# display.net
KiCad netlist of a schematic drawn in EAGLE
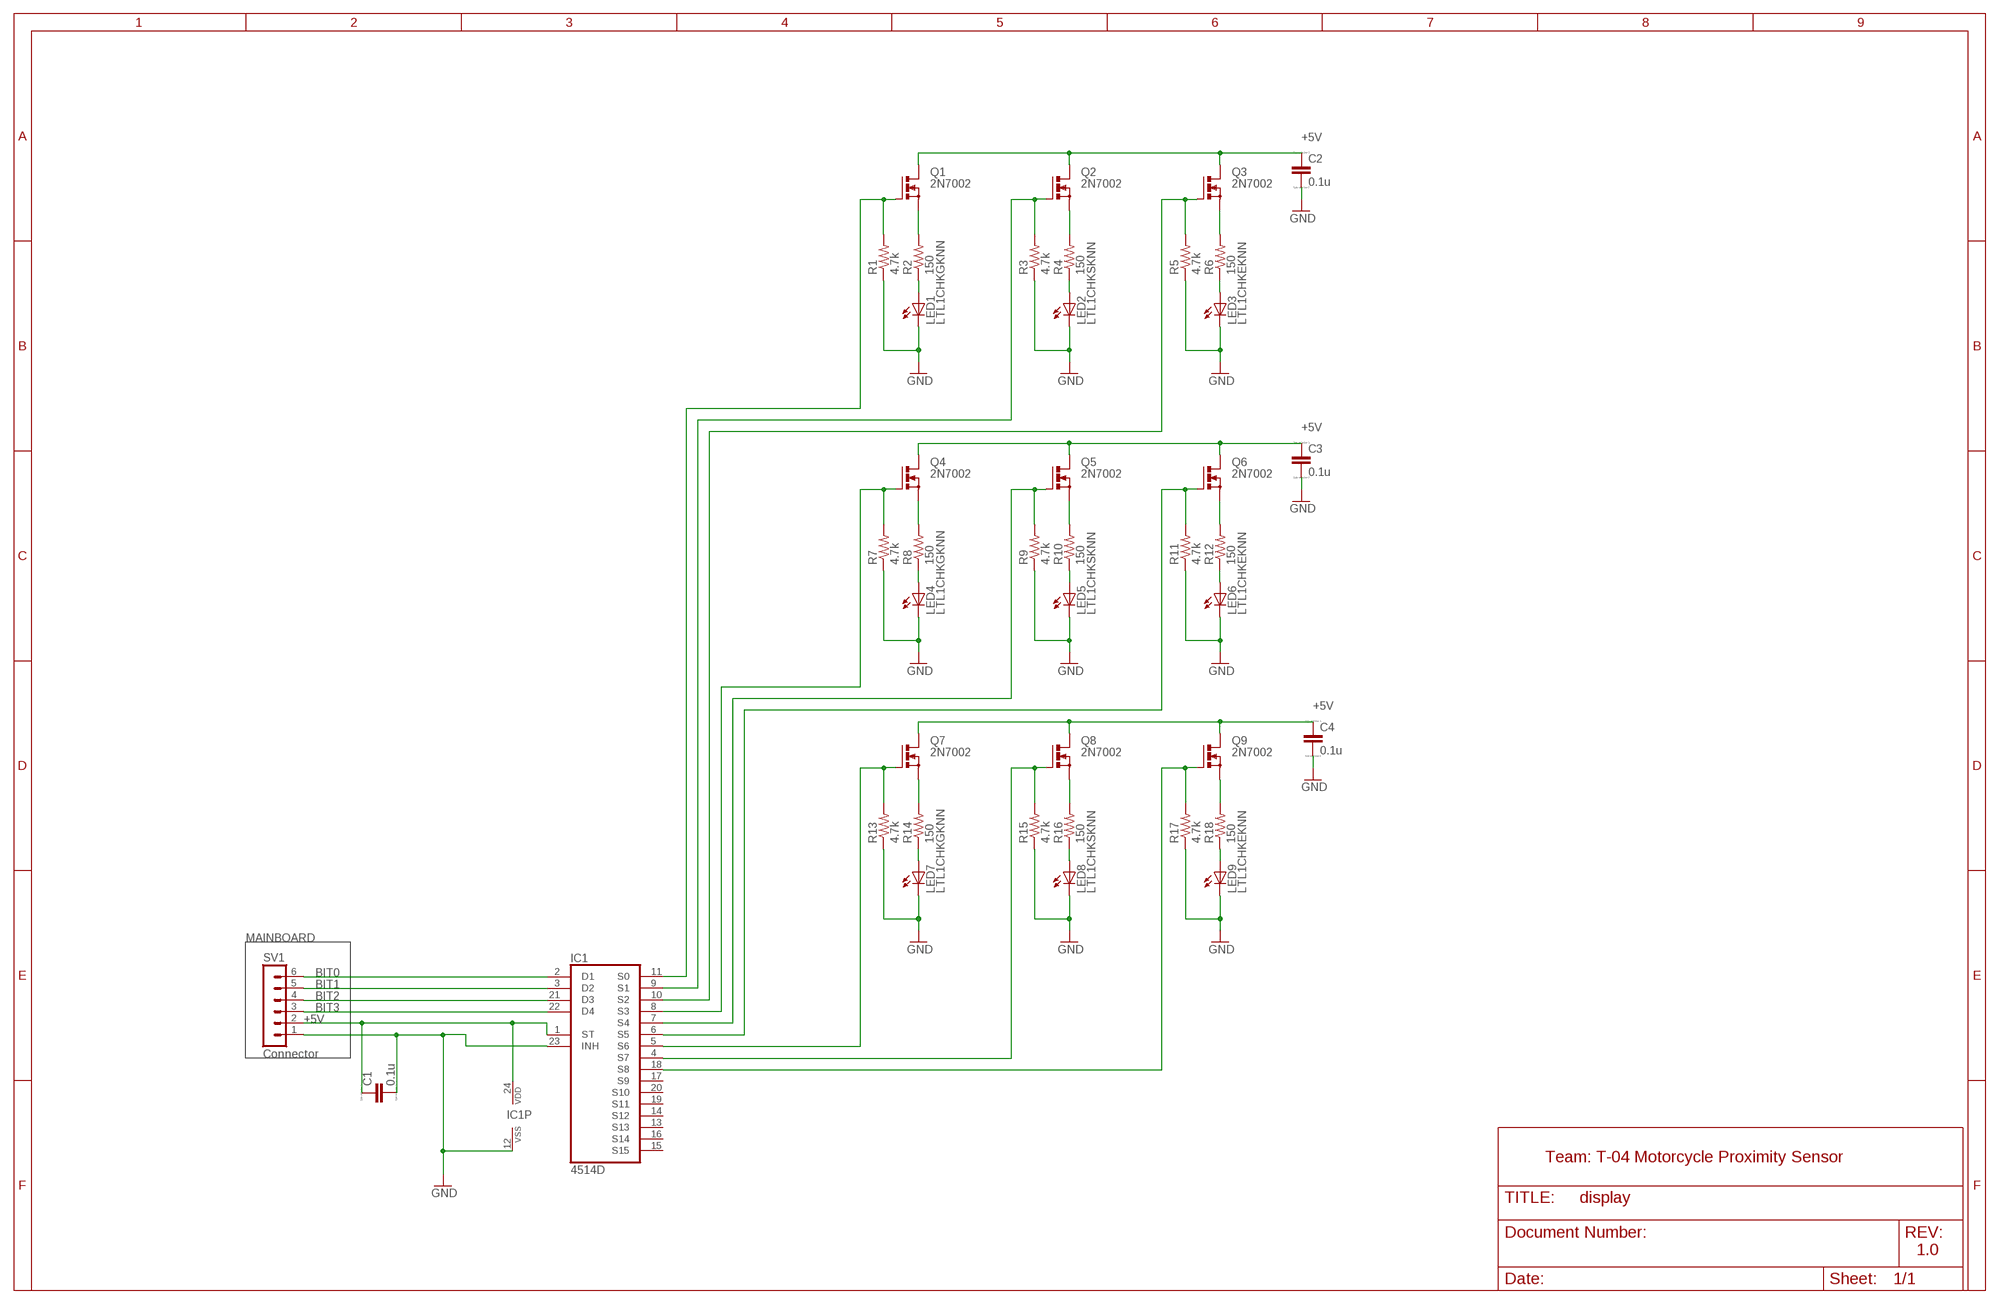
[diagram p0: schematic, sheet 1]

(export (version "E")
  (design (tool "Eeschema 10.0.6"))
  (components
    (comp (ref "C1")
      (value "0.1u")
      (footprint "eagle-import:C3216")
      (libsource (lib "eagle-import") (part "CC3216"))
    )
    (comp (ref "C2")
      (value "0.1u")
      (footprint "eagle-import:C3216")
      (libsource (lib "eagle-import") (part "CC3216"))
    )
    (comp (ref "C3")
      (value "0.1u")
      (footprint "eagle-import:C3216")
      (libsource (lib "eagle-import") (part "CC3216"))
    )
    (comp (ref "C4")
      (value "0.1u")
      (footprint "eagle-import:C3216")
      (libsource (lib "eagle-import") (part "CC3216"))
    )
    (comp (ref "IC1")
      (value "4514D")
      (footprint "eagle-import:SO24W")
      (libsource (lib "eagle-import") (part "4514D"))
    )
    (comp (ref "LED1")
      (value "LTL1CHKGKNN")
      (footprint "eagle-import:1206")
      (libsource (lib "eagle-import") (part "LEDSMT1206"))
    )
    (comp (ref "LED2")
      (value "LTL1CHKSKNN")
      (footprint "eagle-import:1206")
      (libsource (lib "eagle-import") (part "LEDSMT1206"))
    )
    (comp (ref "LED3")
      (value "LTL1CHKEKNN")
      (footprint "eagle-import:1206")
      (libsource (lib "eagle-import") (part "LEDSMT1206"))
    )
    (comp (ref "LED4")
      (value "LTL1CHKGKNN")
      (footprint "eagle-import:1206")
      (libsource (lib "eagle-import") (part "LEDSMT1206"))
    )
    (comp (ref "LED5")
      (value "LTL1CHKSKNN")
      (footprint "eagle-import:1206")
      (libsource (lib "eagle-import") (part "LEDSMT1206"))
    )
    (comp (ref "LED6")
      (value "LTL1CHKEKNN")
      (footprint "eagle-import:1206")
      (libsource (lib "eagle-import") (part "LEDSMT1206"))
    )
    (comp (ref "LED7")
      (value "LTL1CHKGKNN")
      (footprint "eagle-import:1206")
      (libsource (lib "eagle-import") (part "LEDSMT1206"))
    )
    (comp (ref "LED8")
      (value "LTL1CHKSKNN")
      (footprint "eagle-import:1206")
      (libsource (lib "eagle-import") (part "LEDSMT1206"))
    )
    (comp (ref "LED9")
      (value "LTL1CHKEKNN")
      (footprint "eagle-import:1206")
      (libsource (lib "eagle-import") (part "LEDSMT1206"))
    )
    (comp (ref "Q1")
      (value "2N7002")
      (footprint "eagle-import:TO220BV")
      (libsource (lib "eagle-import") (part "BUZ11BV"))
    )
    (comp (ref "Q2")
      (value "2N7002")
      (footprint "eagle-import:TO220BV")
      (libsource (lib "eagle-import") (part "BUZ11BV"))
    )
    (comp (ref "Q3")
      (value "2N7002")
      (footprint "eagle-import:TO220BV")
      (libsource (lib "eagle-import") (part "BUZ11BV"))
    )
    (comp (ref "Q4")
      (value "2N7002")
      (footprint "eagle-import:TO220BV")
      (libsource (lib "eagle-import") (part "BUZ11BV"))
    )
    (comp (ref "Q5")
      (value "2N7002")
      (footprint "eagle-import:TO220BV")
      (libsource (lib "eagle-import") (part "BUZ11BV"))
    )
    (comp (ref "Q6")
      (value "2N7002")
      (footprint "eagle-import:TO220BV")
      (libsource (lib "eagle-import") (part "BUZ11BV"))
    )
    (comp (ref "Q7")
      (value "2N7002")
      (footprint "eagle-import:TO220BV")
      (libsource (lib "eagle-import") (part "BUZ11BV"))
    )
    (comp (ref "Q8")
      (value "2N7002")
      (footprint "eagle-import:TO220BV")
      (libsource (lib "eagle-import") (part "BUZ11BV"))
    )
    (comp (ref "Q9")
      (value "2N7002")
      (footprint "eagle-import:TO220BV")
      (libsource (lib "eagle-import") (part "BUZ11BV"))
    )
    (comp (ref "R1")
      (value "4.7k")
      (footprint "eagle-import:M3516")
      (libsource (lib "eagle-import") (part "R-US_M3516"))
    )
    (comp (ref "R2")
      (value "150")
      (footprint "eagle-import:M3516")
      (libsource (lib "eagle-import") (part "R-US_M3516"))
    )
    (comp (ref "R3")
      (value "4.7k")
      (footprint "eagle-import:M3516")
      (libsource (lib "eagle-import") (part "R-US_M3516"))
    )
    (comp (ref "R4")
      (value "150")
      (footprint "eagle-import:M3516")
      (libsource (lib "eagle-import") (part "R-US_M3516"))
    )
    (comp (ref "R5")
      (value "4.7k")
      (footprint "eagle-import:M3516")
      (libsource (lib "eagle-import") (part "R-US_M3516"))
    )
    (comp (ref "R6")
      (value "150")
      (footprint "eagle-import:M3516")
      (libsource (lib "eagle-import") (part "R-US_M3516"))
    )
    (comp (ref "R7")
      (value "4.7k")
      (footprint "eagle-import:M3516")
      (libsource (lib "eagle-import") (part "R-US_M3516"))
    )
    (comp (ref "R8")
      (value "150")
      (footprint "eagle-import:M3516")
      (libsource (lib "eagle-import") (part "R-US_M3516"))
    )
    (comp (ref "R9")
      (value "4.7k")
      (footprint "eagle-import:M3516")
      (libsource (lib "eagle-import") (part "R-US_M3516"))
    )
    (comp (ref "R10")
      (value "150")
      (footprint "eagle-import:M3516")
      (libsource (lib "eagle-import") (part "R-US_M3516"))
    )
    (comp (ref "R11")
      (value "4.7k")
      (footprint "eagle-import:M3516")
      (libsource (lib "eagle-import") (part "R-US_M3516"))
    )
    (comp (ref "R12")
      (value "150")
      (footprint "eagle-import:M3516")
      (libsource (lib "eagle-import") (part "R-US_M3516"))
    )
    (comp (ref "R13")
      (value "4.7k")
      (footprint "eagle-import:M3516")
      (libsource (lib "eagle-import") (part "R-US_M3516"))
    )
    (comp (ref "R14")
      (value "150")
      (footprint "eagle-import:M3516")
      (libsource (lib "eagle-import") (part "R-US_M3516"))
    )
    (comp (ref "R15")
      (value "4.7k")
      (footprint "eagle-import:M3516")
      (libsource (lib "eagle-import") (part "R-US_M3516"))
    )
    (comp (ref "R16")
      (value "150")
      (footprint "eagle-import:M3516")
      (libsource (lib "eagle-import") (part "R-US_M3516"))
    )
    (comp (ref "R17")
      (value "4.7k")
      (footprint "eagle-import:M3516")
      (libsource (lib "eagle-import") (part "R-US_M3516"))
    )
    (comp (ref "R18")
      (value "150")
      (footprint "eagle-import:M3516")
      (libsource (lib "eagle-import") (part "R-US_M3516"))
    )
    (comp (ref "SV1")
      (value "Connector")
      (footprint "eagle-import:MA06-1")
      (libsource (lib "eagle-import") (part "MA06-1"))
    )
  )
  (nets
    (net (code "1") (name "/+5V") (class "Default")
      (node (ref "C1") (pin "1") (pinfunction "1_1") (pintype "passive"))
      (node (ref "C2") (pin "1") (pinfunction "1_1") (pintype "passive"))
      (node (ref "C3") (pin "1") (pinfunction "1_1") (pintype "passive"))
      (node (ref "C4") (pin "1") (pinfunction "1_1") (pintype "passive"))
      (node (ref "IC1") (pin "1") (pinfunction "ST_1") (pintype "input"))
      (node (ref "IC1") (pin "24") (pinfunction "VDD_24") (pintype "power_in"))
      (node (ref "Q1") (pin "D") (pinfunction "D_D") (pintype "passive"))
      (node (ref "Q2") (pin "D") (pinfunction "D_D") (pintype "passive"))
      (node (ref "Q3") (pin "D") (pinfunction "D_D") (pintype "passive"))
      (node (ref "Q4") (pin "D") (pinfunction "D_D") (pintype "passive"))
      (node (ref "Q5") (pin "D") (pinfunction "D_D") (pintype "passive"))
      (node (ref "Q6") (pin "D") (pinfunction "D_D") (pintype "passive"))
      (node (ref "Q7") (pin "D") (pinfunction "D_D") (pintype "passive"))
      (node (ref "Q8") (pin "D") (pinfunction "D_D") (pintype "passive"))
      (node (ref "Q9") (pin "D") (pinfunction "D_D") (pintype "passive"))
      (node (ref "SV1") (pin "2") (pinfunction "2_2") (pintype "passive"))
    )
    (net (code "2") (name "/BIT0") (class "Default")
      (node (ref "IC1") (pin "2") (pinfunction "D1_2") (pintype "input"))
      (node (ref "SV1") (pin "6") (pinfunction "6_6") (pintype "passive"))
    )
    (net (code "3") (name "/BIT1") (class "Default")
      (node (ref "IC1") (pin "3") (pinfunction "D2_3") (pintype "input"))
      (node (ref "SV1") (pin "5") (pinfunction "5_5") (pintype "passive"))
    )
    (net (code "4") (name "/BIT2") (class "Default")
      (node (ref "IC1") (pin "21") (pinfunction "D3_21") (pintype "input"))
      (node (ref "SV1") (pin "4") (pinfunction "4_4") (pintype "passive"))
    )
    (net (code "5") (name "/BIT3") (class "Default")
      (node (ref "IC1") (pin "22") (pinfunction "D4_22") (pintype "input"))
      (node (ref "SV1") (pin "3") (pinfunction "3_3") (pintype "passive"))
    )
    (net (code "6") (name "GND") (class "Default")
      (node (ref "C1") (pin "2") (pinfunction "2_2") (pintype "passive"))
      (node (ref "C2") (pin "2") (pinfunction "2_2") (pintype "passive"))
      (node (ref "C3") (pin "2") (pinfunction "2_2") (pintype "passive"))
      (node (ref "C4") (pin "2") (pinfunction "2_2") (pintype "passive"))
      (node (ref "IC1") (pin "12") (pinfunction "VSS_12") (pintype "power_in"))
      (node (ref "IC1") (pin "23") (pinfunction "INH_23") (pintype "input"))
      (node (ref "LED1") (pin "C") (pinfunction "C_C") (pintype "passive"))
      (node (ref "LED2") (pin "C") (pinfunction "C_C") (pintype "passive"))
      (node (ref "LED3") (pin "C") (pinfunction "C_C") (pintype "passive"))
      (node (ref "LED4") (pin "C") (pinfunction "C_C") (pintype "passive"))
      (node (ref "LED5") (pin "C") (pinfunction "C_C") (pintype "passive"))
      (node (ref "LED6") (pin "C") (pinfunction "C_C") (pintype "passive"))
      (node (ref "LED7") (pin "C") (pinfunction "C_C") (pintype "passive"))
      (node (ref "LED8") (pin "C") (pinfunction "C_C") (pintype "passive"))
      (node (ref "LED9") (pin "C") (pinfunction "C_C") (pintype "passive"))
      (node (ref "R1") (pin "1") (pinfunction "1_1") (pintype "passive"))
      (node (ref "R11") (pin "1") (pinfunction "1_1") (pintype "passive"))
      (node (ref "R13") (pin "1") (pinfunction "1_1") (pintype "passive"))
      (node (ref "R15") (pin "1") (pinfunction "1_1") (pintype "passive"))
      (node (ref "R17") (pin "1") (pinfunction "1_1") (pintype "passive"))
      (node (ref "R3") (pin "1") (pinfunction "1_1") (pintype "passive"))
      (node (ref "R5") (pin "1") (pinfunction "1_1") (pintype "passive"))
      (node (ref "R7") (pin "1") (pinfunction "1_1") (pintype "passive"))
      (node (ref "R9") (pin "1") (pinfunction "1_1") (pintype "passive"))
      (node (ref "SV1") (pin "1") (pinfunction "1_1") (pintype "passive"))
    )
    (net (code "7") (name "Net-(IC1A-S0)") (class "Default")
      (node (ref "IC1") (pin "11") (pinfunction "S0_11") (pintype "output"))
      (node (ref "Q1") (pin "G") (pinfunction "G_G") (pintype "passive"))
      (node (ref "R1") (pin "2") (pinfunction "2_2") (pintype "passive"))
    )
    (net (code "8") (name "Net-(IC1A-S1)") (class "Default")
      (node (ref "IC1") (pin "9") (pinfunction "S1_9") (pintype "output"))
      (node (ref "Q2") (pin "G") (pinfunction "G_G") (pintype "passive"))
      (node (ref "R3") (pin "2") (pinfunction "2_2") (pintype "passive"))
    )
    (net (code "9") (name "Net-(IC1A-S2)") (class "Default")
      (node (ref "IC1") (pin "10") (pinfunction "S2_10") (pintype "output"))
      (node (ref "Q3") (pin "G") (pinfunction "G_G") (pintype "passive"))
      (node (ref "R5") (pin "2") (pinfunction "2_2") (pintype "passive"))
    )
    (net (code "10") (name "Net-(IC1A-S3)") (class "Default")
      (node (ref "IC1") (pin "8") (pinfunction "S3_8") (pintype "output"))
      (node (ref "Q4") (pin "G") (pinfunction "G_G") (pintype "passive"))
      (node (ref "R7") (pin "2") (pinfunction "2_2") (pintype "passive"))
    )
    (net (code "11") (name "Net-(IC1A-S4)") (class "Default")
      (node (ref "IC1") (pin "7") (pinfunction "S4_7") (pintype "output"))
      (node (ref "Q5") (pin "G") (pinfunction "G_G") (pintype "passive"))
      (node (ref "R9") (pin "2") (pinfunction "2_2") (pintype "passive"))
    )
    (net (code "12") (name "Net-(IC1A-S5)") (class "Default")
      (node (ref "IC1") (pin "6") (pinfunction "S5_6") (pintype "output"))
      (node (ref "Q6") (pin "G") (pinfunction "G_G") (pintype "passive"))
      (node (ref "R11") (pin "2") (pinfunction "2_2") (pintype "passive"))
    )
    (net (code "13") (name "Net-(IC1A-S6)") (class "Default")
      (node (ref "IC1") (pin "5") (pinfunction "S6_5") (pintype "output"))
      (node (ref "Q7") (pin "G") (pinfunction "G_G") (pintype "passive"))
      (node (ref "R13") (pin "2") (pinfunction "2_2") (pintype "passive"))
    )
    (net (code "14") (name "Net-(IC1A-S7)") (class "Default")
      (node (ref "IC1") (pin "4") (pinfunction "S7_4") (pintype "output"))
      (node (ref "Q8") (pin "G") (pinfunction "G_G") (pintype "passive"))
      (node (ref "R15") (pin "2") (pinfunction "2_2") (pintype "passive"))
    )
    (net (code "15") (name "Net-(IC1A-S8)") (class "Default")
      (node (ref "IC1") (pin "18") (pinfunction "S8_18") (pintype "output"))
      (node (ref "Q9") (pin "G") (pinfunction "G_G") (pintype "passive"))
      (node (ref "R17") (pin "2") (pinfunction "2_2") (pintype "passive"))
    )
    (net (code "16") (name "Net-(LED1-PadA)") (class "Default")
      (node (ref "LED1") (pin "A") (pinfunction "A_A") (pintype "passive"))
      (node (ref "R2") (pin "1") (pinfunction "1_1") (pintype "passive"))
    )
    (net (code "17") (name "Net-(LED2-PadA)") (class "Default")
      (node (ref "LED2") (pin "A") (pinfunction "A_A") (pintype "passive"))
      (node (ref "R4") (pin "1") (pinfunction "1_1") (pintype "passive"))
    )
    (net (code "18") (name "Net-(LED3-PadA)") (class "Default")
      (node (ref "LED3") (pin "A") (pinfunction "A_A") (pintype "passive"))
      (node (ref "R6") (pin "1") (pinfunction "1_1") (pintype "passive"))
    )
    (net (code "19") (name "Net-(LED4-PadA)") (class "Default")
      (node (ref "LED4") (pin "A") (pinfunction "A_A") (pintype "passive"))
      (node (ref "R8") (pin "1") (pinfunction "1_1") (pintype "passive"))
    )
    (net (code "20") (name "Net-(LED5-PadA)") (class "Default")
      (node (ref "LED5") (pin "A") (pinfunction "A_A") (pintype "passive"))
      (node (ref "R10") (pin "1") (pinfunction "1_1") (pintype "passive"))
    )
    (net (code "21") (name "Net-(LED6-PadA)") (class "Default")
      (node (ref "LED6") (pin "A") (pinfunction "A_A") (pintype "passive"))
      (node (ref "R12") (pin "1") (pinfunction "1_1") (pintype "passive"))
    )
    (net (code "22") (name "Net-(LED7-PadA)") (class "Default")
      (node (ref "LED7") (pin "A") (pinfunction "A_A") (pintype "passive"))
      (node (ref "R14") (pin "1") (pinfunction "1_1") (pintype "passive"))
    )
    (net (code "23") (name "Net-(LED8-PadA)") (class "Default")
      (node (ref "LED8") (pin "A") (pinfunction "A_A") (pintype "passive"))
      (node (ref "R16") (pin "1") (pinfunction "1_1") (pintype "passive"))
    )
    (net (code "24") (name "Net-(LED9-PadA)") (class "Default")
      (node (ref "LED9") (pin "A") (pinfunction "A_A") (pintype "passive"))
      (node (ref "R18") (pin "1") (pinfunction "1_1") (pintype "passive"))
    )
    (net (code "25") (name "Net-(Q1-PadS)") (class "Default")
      (node (ref "Q1") (pin "S") (pinfunction "S_S") (pintype "passive"))
      (node (ref "R2") (pin "2") (pinfunction "2_2") (pintype "passive"))
    )
    (net (code "26") (name "Net-(Q2-PadS)") (class "Default")
      (node (ref "Q2") (pin "S") (pinfunction "S_S") (pintype "passive"))
      (node (ref "R4") (pin "2") (pinfunction "2_2") (pintype "passive"))
    )
    (net (code "27") (name "Net-(Q3-PadS)") (class "Default")
      (node (ref "Q3") (pin "S") (pinfunction "S_S") (pintype "passive"))
      (node (ref "R6") (pin "2") (pinfunction "2_2") (pintype "passive"))
    )
    (net (code "28") (name "Net-(Q4-PadS)") (class "Default")
      (node (ref "Q4") (pin "S") (pinfunction "S_S") (pintype "passive"))
      (node (ref "R8") (pin "2") (pinfunction "2_2") (pintype "passive"))
    )
    (net (code "29") (name "Net-(Q5-PadS)") (class "Default")
      (node (ref "Q5") (pin "S") (pinfunction "S_S") (pintype "passive"))
      (node (ref "R10") (pin "2") (pinfunction "2_2") (pintype "passive"))
    )
    (net (code "30") (name "Net-(Q6-PadS)") (class "Default")
      (node (ref "Q6") (pin "S") (pinfunction "S_S") (pintype "passive"))
      (node (ref "R12") (pin "2") (pinfunction "2_2") (pintype "passive"))
    )
    (net (code "31") (name "Net-(Q7-PadS)") (class "Default")
      (node (ref "Q7") (pin "S") (pinfunction "S_S") (pintype "passive"))
      (node (ref "R14") (pin "2") (pinfunction "2_2") (pintype "passive"))
    )
    (net (code "32") (name "Net-(Q8-PadS)") (class "Default")
      (node (ref "Q8") (pin "S") (pinfunction "S_S") (pintype "passive"))
      (node (ref "R16") (pin "2") (pinfunction "2_2") (pintype "passive"))
    )
    (net (code "33") (name "Net-(Q9-PadS)") (class "Default")
      (node (ref "Q9") (pin "S") (pinfunction "S_S") (pintype "passive"))
      (node (ref "R18") (pin "2") (pinfunction "2_2") (pintype "passive"))
    )
    (net (code "34") (name "unconnected-(IC1A-S9-Pad17)") (class "Default")
      (node (ref "IC1") (pin "17") (pinfunction "S9_17") (pintype "output"))
    )
    (net (code "35") (name "unconnected-(IC1A-S10-Pad20)") (class "Default")
      (node (ref "IC1") (pin "20") (pinfunction "S10_20") (pintype "output"))
    )
    (net (code "36") (name "unconnected-(IC1A-S11-Pad19)") (class "Default")
      (node (ref "IC1") (pin "19") (pinfunction "S11_19") (pintype "output"))
    )
    (net (code "37") (name "unconnected-(IC1A-S12-Pad14)") (class "Default")
      (node (ref "IC1") (pin "14") (pinfunction "S12_14") (pintype "output"))
    )
    (net (code "38") (name "unconnected-(IC1A-S13-Pad13)") (class "Default")
      (node (ref "IC1") (pin "13") (pinfunction "S13_13") (pintype "output"))
    )
    (net (code "39") (name "unconnected-(IC1A-S14-Pad16)") (class "Default")
      (node (ref "IC1") (pin "16") (pinfunction "S14_16") (pintype "output"))
    )
    (net (code "40") (name "unconnected-(IC1A-S15-Pad15)") (class "Default")
      (node (ref "IC1") (pin "15") (pinfunction "S15_15") (pintype "output"))
    )
  )
)
